# 12VRGBCW.net
KiCad netlist of a schematic drawn in Altium Designer
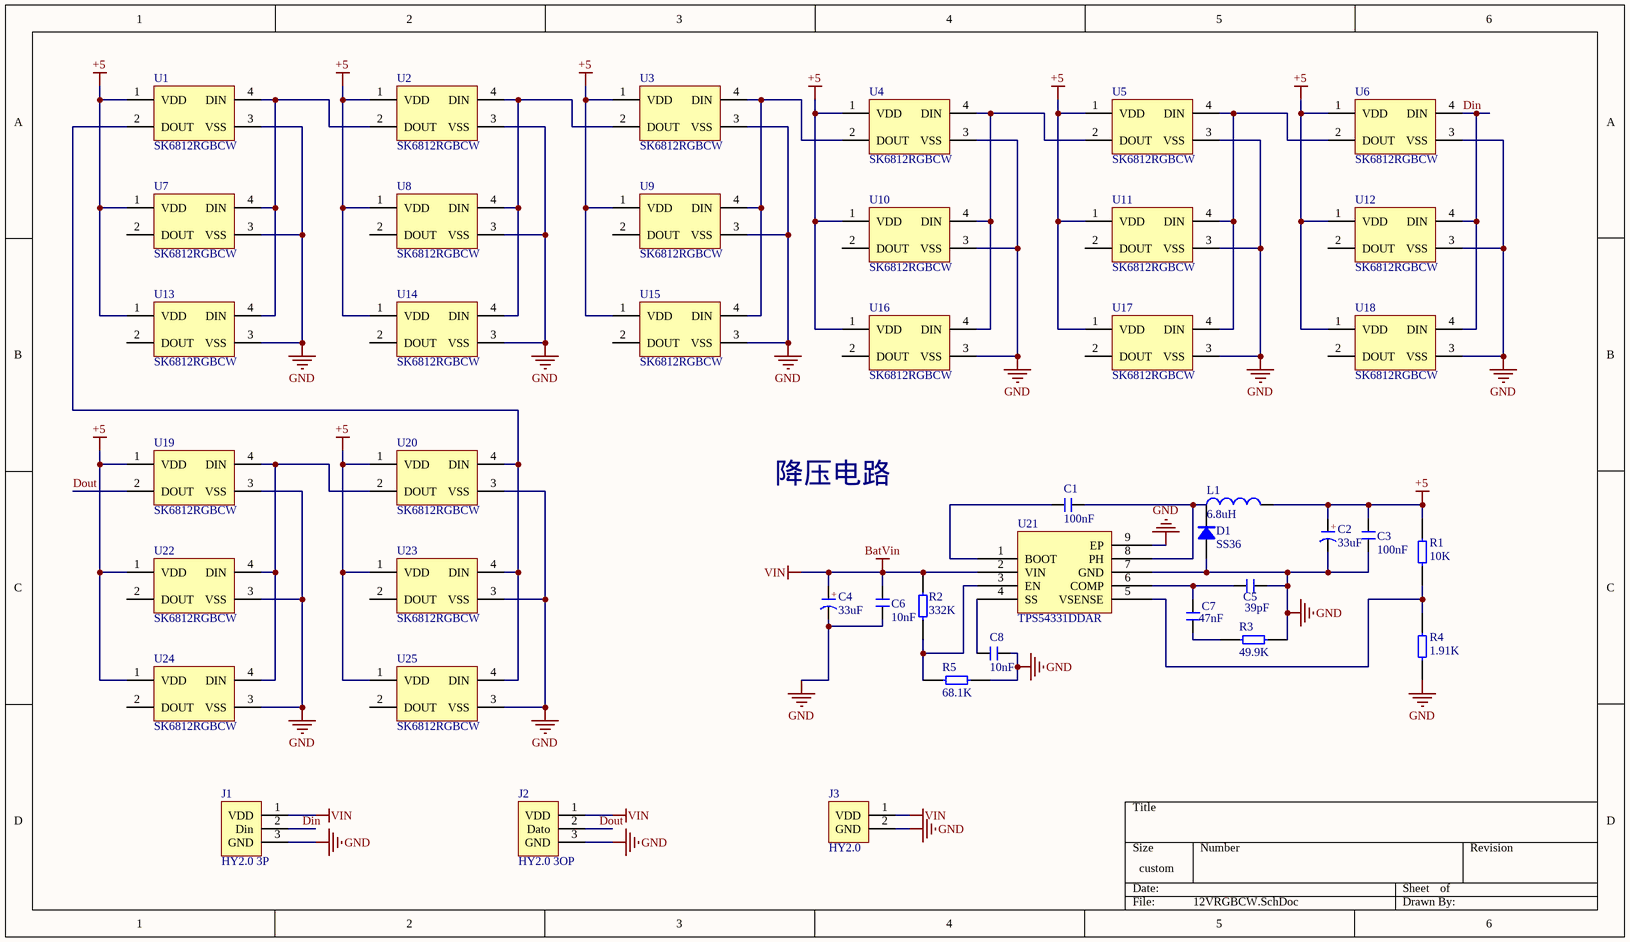
[diagram p0: 12VRGBCW.SchDoc]

(export (version "E")
  (design (tool "Eeschema 10.0.6"))
  (components
    (comp (ref "C1")
      (value "100nF")
      (footprint "C 0603_L")
      (description "无极性贴片电容")
      (libsource (lib "stm32底盘_PCB_V1.0") (part "C"))
    )
    (comp (ref "C2")
      (value "33uF")
      (footprint "CM D(6.3*5.4)")
      (description "直插固态电容")
      (libsource (lib "stm32底盘_PCB_V1.0") (part "C-CS"))
    )
    (comp (ref "C3")
      (value "100nF")
      (footprint "C 0603_M")
      (description "无极性贴片电容")
      (libsource (lib "stm32底盘_PCB_V1.0") (part "C"))
    )
    (comp (ref "C4")
      (value "33uF")
      (footprint "CM D(6.3*5.4)")
      (description "直插固态电容")
      (libsource (lib "stm32底盘_PCB_V1.0") (part "C-CS"))
    )
    (comp (ref "C5")
      (value "39pF")
      (footprint "C 0603_L")
      (description "无极性贴片电容")
      (libsource (lib "stm32底盘_PCB_V1.0") (part "C"))
    )
    (comp (ref "C6")
      (value "10nF")
      (footprint "C 0603_L")
      (description "无极性贴片电容")
      (libsource (lib "stm32底盘_PCB_V1.0") (part "C"))
    )
    (comp (ref "C7")
      (value "47nF")
      (footprint "C 0603_L")
      (description "无极性贴片电容")
      (libsource (lib "stm32底盘_PCB_V1.0") (part "C"))
    )
    (comp (ref "C8")
      (value "10nF")
      (footprint "C 0603_L")
      (description "无极性贴片电容")
      (libsource (lib "stm32底盘_PCB_V1.0") (part "C"))
    )
    (comp (ref "D1")
      (value "SS36")
      (footprint "SMA")
      (description "肖特基二极管")
      (libsource (lib "stm32底盘_PCB_V1.0") (part "SS36"))
    )
    (comp (ref "J1") (value "HY2.0 3P") (description "数据输入") (libsource (lib "12VRGBCW") (part "HY2.0 3P")))
    (comp (ref "J2") (value "HY2.0 3OP") (libsource (lib "12VRGBCW") (part "HY2.0 3OP")))
    (comp (ref "J3") (value "HY2.0") (description "供电接口") (libsource (lib "12VRGBCW") (part "HY2.0")))
    (comp (ref "L1")
      (value "6.8uH")
      (footprint "CDRH73")
      (description "小功率贴片电感")
      (libsource (lib "stm32底盘_PCB_V1.0") (part "L"))
    )
    (comp (ref "R1")
      (value "10K")
      (footprint "R 0603_M")
      (description "电阻")
      (libsource (lib "stm32底盘_PCB_V1.0") (part "Res"))
    )
    (comp (ref "R2")
      (value "332K")
      (footprint "R 0603_M")
      (description "电阻")
      (libsource (lib "stm32底盘_PCB_V1.0") (part "Res"))
    )
    (comp (ref "R3")
      (value "49.9K")
      (footprint "R 0603_M")
      (description "电阻")
      (libsource (lib "stm32底盘_PCB_V1.0") (part "Res"))
    )
    (comp (ref "R4")
      (value "1.91K")
      (footprint "R 0603_M")
      (description "电阻")
      (libsource (lib "stm32底盘_PCB_V1.0") (part "Res"))
    )
    (comp (ref "R5")
      (value "68.1K")
      (footprint "R 0603_M")
      (description "电阻")
      (libsource (lib "stm32底盘_PCB_V1.0") (part "Res"))
    )
    (comp (ref "U1")
      (value "SK6812RGBCW")
      (description "RGB灯珠")
      (libsource (lib "12VRGBCW") (part "SK6812RGBCW"))
    )
    (comp (ref "U2")
      (value "SK6812RGBCW")
      (description "RGB灯珠")
      (libsource (lib "12VRGBCW") (part "SK6812RGBCW"))
    )
    (comp (ref "U3")
      (value "SK6812RGBCW")
      (description "RGB灯珠")
      (libsource (lib "12VRGBCW") (part "SK6812RGBCW"))
    )
    (comp (ref "U4")
      (value "SK6812RGBCW")
      (description "RGB灯珠")
      (libsource (lib "12VRGBCW") (part "SK6812RGBCW"))
    )
    (comp (ref "U5")
      (value "SK6812RGBCW")
      (description "RGB灯珠")
      (libsource (lib "12VRGBCW") (part "SK6812RGBCW"))
    )
    (comp (ref "U6")
      (value "SK6812RGBCW")
      (description "RGB灯珠")
      (libsource (lib "12VRGBCW") (part "SK6812RGBCW"))
    )
    (comp (ref "U7")
      (value "SK6812RGBCW")
      (description "RGB灯珠")
      (libsource (lib "12VRGBCW") (part "SK6812RGBCW"))
    )
    (comp (ref "U8")
      (value "SK6812RGBCW")
      (description "RGB灯珠")
      (libsource (lib "12VRGBCW") (part "SK6812RGBCW"))
    )
    (comp (ref "U9")
      (value "SK6812RGBCW")
      (description "RGB灯珠")
      (libsource (lib "12VRGBCW") (part "SK6812RGBCW"))
    )
    (comp (ref "U10")
      (value "SK6812RGBCW")
      (description "RGB灯珠")
      (libsource (lib "12VRGBCW") (part "SK6812RGBCW"))
    )
    (comp (ref "U11")
      (value "SK6812RGBCW")
      (description "RGB灯珠")
      (libsource (lib "12VRGBCW") (part "SK6812RGBCW"))
    )
    (comp (ref "U12")
      (value "SK6812RGBCW")
      (description "RGB灯珠")
      (libsource (lib "12VRGBCW") (part "SK6812RGBCW"))
    )
    (comp (ref "U13")
      (value "SK6812RGBCW")
      (description "RGB灯珠")
      (libsource (lib "12VRGBCW") (part "SK6812RGBCW"))
    )
    (comp (ref "U14")
      (value "SK6812RGBCW")
      (description "RGB灯珠")
      (libsource (lib "12VRGBCW") (part "SK6812RGBCW"))
    )
    (comp (ref "U15")
      (value "SK6812RGBCW")
      (description "RGB灯珠")
      (libsource (lib "12VRGBCW") (part "SK6812RGBCW"))
    )
    (comp (ref "U16")
      (value "SK6812RGBCW")
      (description "RGB灯珠")
      (libsource (lib "12VRGBCW") (part "SK6812RGBCW"))
    )
    (comp (ref "U17")
      (value "SK6812RGBCW")
      (description "RGB灯珠")
      (libsource (lib "12VRGBCW") (part "SK6812RGBCW"))
    )
    (comp (ref "U18")
      (value "SK6812RGBCW")
      (description "RGB灯珠")
      (libsource (lib "12VRGBCW") (part "SK6812RGBCW"))
    )
    (comp (ref "U19")
      (value "SK6812RGBCW")
      (description "RGB灯珠")
      (libsource (lib "12VRGBCW") (part "SK6812RGBCW"))
    )
    (comp (ref "U20")
      (value "SK6812RGBCW")
      (description "RGB灯珠")
      (libsource (lib "12VRGBCW") (part "SK6812RGBCW"))
    )
    (comp (ref "U21")
      (value "TPS54331DDAR")
      (footprint "SOP8_M")
      (description "压降芯片")
      (libsource (lib "stm32底盘_PCB_V1.0") (part "TPS54331DDAR"))
    )
    (comp (ref "U22")
      (value "SK6812RGBCW")
      (description "RGB灯珠")
      (libsource (lib "12VRGBCW") (part "SK6812RGBCW"))
    )
    (comp (ref "U23")
      (value "SK6812RGBCW")
      (description "RGB灯珠")
      (libsource (lib "12VRGBCW") (part "SK6812RGBCW"))
    )
    (comp (ref "U24")
      (value "SK6812RGBCW")
      (description "RGB灯珠")
      (libsource (lib "12VRGBCW") (part "SK6812RGBCW"))
    )
    (comp (ref "U25")
      (value "SK6812RGBCW")
      (description "RGB灯珠")
      (libsource (lib "12VRGBCW") (part "SK6812RGBCW"))
    )
  )
  (nets
    (net (code "1") (name "+5") (class "Default")
      (node (ref "C2") (pin "1") (pinfunction "A_1") (pintype "passive"))
      (node (ref "C3") (pin "2") (pinfunction "2_2") (pintype "passive"))
      (node (ref "L1") (pin "2") (pinfunction "2_2") (pintype "passive"))
      (node (ref "R1") (pin "2") (pintype "passive"))
      (node (ref "U1") (pin "1") (pinfunction "VDD_1") (pintype "passive"))
      (node (ref "U10") (pin "1") (pinfunction "VDD_1") (pintype "passive"))
      (node (ref "U11") (pin "1") (pinfunction "VDD_1") (pintype "passive"))
      (node (ref "U12") (pin "1") (pinfunction "VDD_1") (pintype "passive"))
      (node (ref "U13") (pin "1") (pinfunction "VDD_1") (pintype "passive"))
      (node (ref "U14") (pin "1") (pinfunction "VDD_1") (pintype "passive"))
      (node (ref "U15") (pin "1") (pinfunction "VDD_1") (pintype "passive"))
      (node (ref "U16") (pin "1") (pinfunction "VDD_1") (pintype "passive"))
      (node (ref "U17") (pin "1") (pinfunction "VDD_1") (pintype "passive"))
      (node (ref "U18") (pin "1") (pinfunction "VDD_1") (pintype "passive"))
      (node (ref "U19") (pin "1") (pinfunction "VDD_1") (pintype "passive"))
      (node (ref "U2") (pin "1") (pinfunction "VDD_1") (pintype "passive"))
      (node (ref "U20") (pin "1") (pinfunction "VDD_1") (pintype "passive"))
      (node (ref "U22") (pin "1") (pinfunction "VDD_1") (pintype "passive"))
      (node (ref "U23") (pin "1") (pinfunction "VDD_1") (pintype "passive"))
      (node (ref "U24") (pin "1") (pinfunction "VDD_1") (pintype "passive"))
      (node (ref "U25") (pin "1") (pinfunction "VDD_1") (pintype "passive"))
      (node (ref "U3") (pin "1") (pinfunction "VDD_1") (pintype "passive"))
      (node (ref "U4") (pin "1") (pinfunction "VDD_1") (pintype "passive"))
      (node (ref "U5") (pin "1") (pinfunction "VDD_1") (pintype "passive"))
      (node (ref "U6") (pin "1") (pinfunction "VDD_1") (pintype "passive"))
      (node (ref "U7") (pin "1") (pinfunction "VDD_1") (pintype "passive"))
      (node (ref "U8") (pin "1") (pinfunction "VDD_1") (pintype "passive"))
      (node (ref "U9") (pin "1") (pinfunction "VDD_1") (pintype "passive"))
    )
    (net (code "2") (name "/Din") (class "Default")
      (node (ref "J1") (pin "2") (pinfunction "Din_2") (pintype "passive"))
      (node (ref "U12") (pin "4") (pinfunction "DIN_4") (pintype "passive"))
      (node (ref "U18") (pin "4") (pinfunction "DIN_4") (pintype "passive"))
      (node (ref "U6") (pin "4") (pinfunction "DIN_4") (pintype "passive"))
    )
    (net (code "3") (name "/Dout") (class "Default")
      (node (ref "J2") (pin "2") (pinfunction "Dato_2") (pintype "passive"))
      (node (ref "U19") (pin "2") (pinfunction "DOUT_2") (pintype "passive"))
    )
    (net (code "4") (name "BatVin") (class "Default")
      (node (ref "C4") (pin "1") (pinfunction "A_1") (pintype "passive"))
      (node (ref "C6") (pin "2") (pinfunction "2_2") (pintype "passive"))
      (node (ref "J1") (pin "1") (pinfunction "VDD_1") (pintype "passive"))
      (node (ref "J2") (pin "1") (pinfunction "VDD_1") (pintype "passive"))
      (node (ref "J3") (pin "1") (pinfunction "VDD_1") (pintype "passive"))
      (node (ref "R2") (pin "1") (pintype "passive"))
      (node (ref "U21") (pin "2") (pinfunction "VIN_2") (pintype "passive"))
    )
    (net (code "5") (name "GND") (class "Default")
      (node (ref "C2") (pin "2") (pinfunction "K_2") (pintype "passive"))
      (node (ref "C3") (pin "1") (pinfunction "1_1") (pintype "passive"))
      (node (ref "C4") (pin "2") (pinfunction "K_2") (pintype "passive"))
      (node (ref "C5") (pin "1") (pinfunction "1_1") (pintype "passive"))
      (node (ref "C6") (pin "1") (pinfunction "1_1") (pintype "passive"))
      (node (ref "C8") (pin "1") (pinfunction "1_1") (pintype "passive"))
      (node (ref "D1") (pin "1") (pinfunction "A_1") (pintype "passive"))
      (node (ref "J1") (pin "3") (pinfunction "GND_3") (pintype "passive"))
      (node (ref "J2") (pin "3") (pinfunction "GND_3") (pintype "passive"))
      (node (ref "J3") (pin "2") (pinfunction "GND_2") (pintype "passive"))
      (node (ref "R3") (pin "2") (pintype "passive"))
      (node (ref "R4") (pin "1") (pintype "passive"))
      (node (ref "R5") (pin "2") (pintype "passive"))
      (node (ref "U1") (pin "3") (pinfunction "VSS_3") (pintype "passive"))
      (node (ref "U10") (pin "3") (pinfunction "VSS_3") (pintype "passive"))
      (node (ref "U11") (pin "3") (pinfunction "VSS_3") (pintype "passive"))
      (node (ref "U12") (pin "3") (pinfunction "VSS_3") (pintype "passive"))
      (node (ref "U13") (pin "3") (pinfunction "VSS_3") (pintype "passive"))
      (node (ref "U14") (pin "3") (pinfunction "VSS_3") (pintype "passive"))
      (node (ref "U15") (pin "3") (pinfunction "VSS_3") (pintype "passive"))
      (node (ref "U16") (pin "3") (pinfunction "VSS_3") (pintype "passive"))
      (node (ref "U17") (pin "3") (pinfunction "VSS_3") (pintype "passive"))
      (node (ref "U18") (pin "3") (pinfunction "VSS_3") (pintype "passive"))
      (node (ref "U19") (pin "3") (pinfunction "VSS_3") (pintype "passive"))
      (node (ref "U2") (pin "3") (pinfunction "VSS_3") (pintype "passive"))
      (node (ref "U20") (pin "3") (pinfunction "VSS_3") (pintype "passive"))
      (node (ref "U21") (pin "7") (pinfunction "GND_7") (pintype "passive"))
      (node (ref "U21") (pin "9") (pinfunction "EP_9") (pintype "passive"))
      (node (ref "U22") (pin "3") (pinfunction "VSS_3") (pintype "passive"))
      (node (ref "U23") (pin "3") (pinfunction "VSS_3") (pintype "passive"))
      (node (ref "U24") (pin "3") (pinfunction "VSS_3") (pintype "passive"))
      (node (ref "U25") (pin "3") (pinfunction "VSS_3") (pintype "passive"))
      (node (ref "U3") (pin "3") (pinfunction "VSS_3") (pintype "passive"))
      (node (ref "U4") (pin "3") (pinfunction "VSS_3") (pintype "passive"))
      (node (ref "U5") (pin "3") (pinfunction "VSS_3") (pintype "passive"))
      (node (ref "U6") (pin "3") (pinfunction "VSS_3") (pintype "passive"))
      (node (ref "U7") (pin "3") (pinfunction "VSS_3") (pintype "passive"))
      (node (ref "U8") (pin "3") (pinfunction "VSS_3") (pintype "passive"))
      (node (ref "U9") (pin "3") (pinfunction "VSS_3") (pintype "passive"))
    )
    (net (code "6") (name "Net-(C7-Pad1)") (class "Default")
      (node (ref "C7") (pin "1") (pinfunction "1_1") (pintype "passive"))
      (node (ref "R3") (pin "1") (pintype "passive"))
    )
    (net (code "7") (name "Net-(D1-K)") (class "Default")
      (node (ref "C1") (pin "2") (pinfunction "2_2") (pintype "passive"))
      (node (ref "D1") (pin "2") (pinfunction "K_2") (pintype "passive"))
      (node (ref "L1") (pin "1") (pinfunction "1_1") (pintype "passive"))
      (node (ref "U21") (pin "8") (pinfunction "PH_8") (pintype "passive"))
    )
    (net (code "8") (name "Net-(U1-DIN)") (class "Default")
      (node (ref "U1") (pin "4") (pinfunction "DIN_4") (pintype "passive"))
      (node (ref "U13") (pin "4") (pinfunction "DIN_4") (pintype "passive"))
      (node (ref "U2") (pin "2") (pinfunction "DOUT_2") (pintype "passive"))
      (node (ref "U7") (pin "4") (pinfunction "DIN_4") (pintype "passive"))
    )
    (net (code "9") (name "Net-(U1-DOUT)") (class "Default")
      (node (ref "U1") (pin "2") (pinfunction "DOUT_2") (pintype "passive"))
      (node (ref "U20") (pin "4") (pinfunction "DIN_4") (pintype "passive"))
      (node (ref "U23") (pin "4") (pinfunction "DIN_4") (pintype "passive"))
      (node (ref "U25") (pin "4") (pinfunction "DIN_4") (pintype "passive"))
    )
    (net (code "10") (name "Net-(U10-DIN)") (class "Default")
      (node (ref "U10") (pin "4") (pinfunction "DIN_4") (pintype "passive"))
      (node (ref "U16") (pin "4") (pinfunction "DIN_4") (pintype "passive"))
      (node (ref "U4") (pin "4") (pinfunction "DIN_4") (pintype "passive"))
      (node (ref "U5") (pin "2") (pinfunction "DOUT_2") (pintype "passive"))
    )
    (net (code "11") (name "Net-(U11-DIN)") (class "Default")
      (node (ref "U11") (pin "4") (pinfunction "DIN_4") (pintype "passive"))
      (node (ref "U17") (pin "4") (pinfunction "DIN_4") (pintype "passive"))
      (node (ref "U5") (pin "4") (pinfunction "DIN_4") (pintype "passive"))
      (node (ref "U6") (pin "2") (pinfunction "DOUT_2") (pintype "passive"))
    )
    (net (code "12") (name "Net-(U14-DIN)") (class "Default")
      (node (ref "U14") (pin "4") (pinfunction "DIN_4") (pintype "passive"))
      (node (ref "U2") (pin "4") (pinfunction "DIN_4") (pintype "passive"))
      (node (ref "U3") (pin "2") (pinfunction "DOUT_2") (pintype "passive"))
      (node (ref "U8") (pin "4") (pinfunction "DIN_4") (pintype "passive"))
    )
    (net (code "13") (name "Net-(U15-DIN)") (class "Default")
      (node (ref "U15") (pin "4") (pinfunction "DIN_4") (pintype "passive"))
      (node (ref "U3") (pin "4") (pinfunction "DIN_4") (pintype "passive"))
      (node (ref "U4") (pin "2") (pinfunction "DOUT_2") (pintype "passive"))
      (node (ref "U9") (pin "4") (pinfunction "DIN_4") (pintype "passive"))
    )
    (net (code "14") (name "Net-(U19-DIN)") (class "Default")
      (node (ref "U19") (pin "4") (pinfunction "DIN_4") (pintype "passive"))
      (node (ref "U20") (pin "2") (pinfunction "DOUT_2") (pintype "passive"))
      (node (ref "U22") (pin "4") (pinfunction "DIN_4") (pintype "passive"))
      (node (ref "U24") (pin "4") (pinfunction "DIN_4") (pintype "passive"))
    )
    (net (code "15") (name "Net-(U21-BOOT)") (class "Default")
      (node (ref "C1") (pin "1") (pinfunction "1_1") (pintype "passive"))
      (node (ref "U21") (pin "1") (pinfunction "BOOT_1") (pintype "passive"))
    )
    (net (code "16") (name "Net-(U21-COMP)") (class "Default")
      (node (ref "C5") (pin "2") (pinfunction "2_2") (pintype "passive"))
      (node (ref "C7") (pin "2") (pinfunction "2_2") (pintype "passive"))
      (node (ref "U21") (pin "6") (pinfunction "COMP_6") (pintype "passive"))
    )
    (net (code "17") (name "Net-(U21-EN)") (class "Default")
      (node (ref "R2") (pin "2") (pintype "passive"))
      (node (ref "R5") (pin "1") (pintype "passive"))
      (node (ref "U21") (pin "3") (pinfunction "EN_3") (pintype "passive"))
    )
    (net (code "18") (name "Net-(U21-SS)") (class "Default")
      (node (ref "C8") (pin "2") (pinfunction "2_2") (pintype "passive"))
      (node (ref "U21") (pin "4") (pinfunction "SS_4") (pintype "passive"))
    )
    (net (code "19") (name "Net-(U21-VSENSE)") (class "Default")
      (node (ref "R1") (pin "1") (pintype "passive"))
      (node (ref "R4") (pin "2") (pintype "passive"))
      (node (ref "U21") (pin "5") (pinfunction "VSENSE_5") (pintype "passive"))
    )
    (net (code "20") (name "unconnected-(U7-DOUT-Pad2)") (class "Default")
      (node (ref "U7") (pin "2") (pinfunction "DOUT_2") (pintype "passive"))
    )
    (net (code "21") (name "unconnected-(U8-DOUT-Pad2)") (class "Default")
      (node (ref "U8") (pin "2") (pinfunction "DOUT_2") (pintype "passive"))
    )
    (net (code "22") (name "unconnected-(U9-DOUT-Pad2)") (class "Default")
      (node (ref "U9") (pin "2") (pinfunction "DOUT_2") (pintype "passive"))
    )
    (net (code "23") (name "unconnected-(U10-DOUT-Pad2)") (class "Default")
      (node (ref "U10") (pin "2") (pinfunction "DOUT_2") (pintype "passive"))
    )
    (net (code "24") (name "unconnected-(U11-DOUT-Pad2)") (class "Default")
      (node (ref "U11") (pin "2") (pinfunction "DOUT_2") (pintype "passive"))
    )
    (net (code "25") (name "unconnected-(U12-DOUT-Pad2)") (class "Default")
      (node (ref "U12") (pin "2") (pinfunction "DOUT_2") (pintype "passive"))
    )
    (net (code "26") (name "unconnected-(U13-DOUT-Pad2)") (class "Default")
      (node (ref "U13") (pin "2") (pinfunction "DOUT_2") (pintype "passive"))
    )
    (net (code "27") (name "unconnected-(U14-DOUT-Pad2)") (class "Default")
      (node (ref "U14") (pin "2") (pinfunction "DOUT_2") (pintype "passive"))
    )
    (net (code "28") (name "unconnected-(U15-DOUT-Pad2)") (class "Default")
      (node (ref "U15") (pin "2") (pinfunction "DOUT_2") (pintype "passive"))
    )
    (net (code "29") (name "unconnected-(U16-DOUT-Pad2)") (class "Default")
      (node (ref "U16") (pin "2") (pinfunction "DOUT_2") (pintype "passive"))
    )
    (net (code "30") (name "unconnected-(U17-DOUT-Pad2)") (class "Default")
      (node (ref "U17") (pin "2") (pinfunction "DOUT_2") (pintype "passive"))
    )
    (net (code "31") (name "unconnected-(U18-DOUT-Pad2)") (class "Default")
      (node (ref "U18") (pin "2") (pinfunction "DOUT_2") (pintype "passive"))
    )
    (net (code "32") (name "unconnected-(U22-DOUT-Pad2)") (class "Default")
      (node (ref "U22") (pin "2") (pinfunction "DOUT_2") (pintype "passive"))
    )
    (net (code "33") (name "unconnected-(U23-DOUT-Pad2)") (class "Default")
      (node (ref "U23") (pin "2") (pinfunction "DOUT_2") (pintype "passive"))
    )
    (net (code "34") (name "unconnected-(U24-DOUT-Pad2)") (class "Default")
      (node (ref "U24") (pin "2") (pinfunction "DOUT_2") (pintype "passive"))
    )
    (net (code "35") (name "unconnected-(U25-DOUT-Pad2)") (class "Default")
      (node (ref "U25") (pin "2") (pinfunction "DOUT_2") (pintype "passive"))
    )
  )
)
